# Schematic.net
KiCad netlist of a schematic drawn in Altium Designer
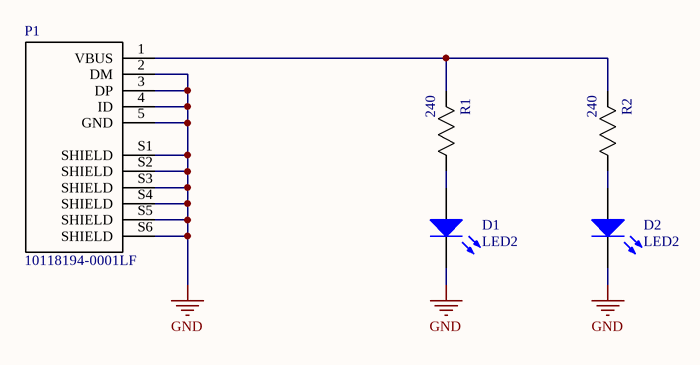
[diagram p0: Schematic.SchDoc]

(export (version "E")
  (design (tool "Eeschema 10.0.6"))
  (components
    (comp (ref "D1")
      (value "LED2")
      (footprint "3.2X1.6X1.1")
      (description "Typical RED, GREEN, YELLOW, AMBER GaAs LED")
      (libsource (lib "AltiumLibraries") (part "LED RED SMD"))
    )
    (comp (ref "D2")
      (value "LED2")
      (footprint "3.2X1.6X1.1")
      (description "Typical RED, GREEN, YELLOW, AMBER GaAs LED")
      (libsource (lib "AltiumLibraries") (part "LED RED SMD"))
    )
    (comp (ref "P1")
      (value "10118194-0001LF")
      (footprint "USB Micro B Receptacle")
      (description "USB - micro B USB 2.0 Receptacle Connector 5 Position Surface Mount, Right Angle; Through Hole")
      (fields (field (name "MF") "Amphenol ICC (FCI)"))
      (libsource (lib "AltiumLibraries") (part "USB Micro B Receptacle"))
    )
    (comp (ref "R1")
      (value "240")
      (footprint "0805")
      (description "RES SMD 240 OHM 5% 1/8W 0805")
      (fields (field (name "TOLERANCE") "5%"))
      (libsource (lib "AltiumLibraries") (part "RES 240.0 1/8W"))
    )
    (comp (ref "R2")
      (value "240")
      (footprint "0805")
      (description "RES SMD 240 OHM 5% 1/8W 0805")
      (fields (field (name "TOLERANCE") "5%"))
      (libsource (lib "AltiumLibraries") (part "RES 240.0 1/8W"))
    )
  )
  (nets
    (net (code "1") (name "GND") (class "Default")
      (node (ref "D1") (pin "2") (pinfunction "K_2") (pintype "passive"))
      (node (ref "D2") (pin "2") (pinfunction "K_2") (pintype "passive"))
      (node (ref "P1") (pin "2") (pinfunction "DM_2") (pintype "passive"))
      (node (ref "P1") (pin "3") (pinfunction "DP_3") (pintype "passive"))
      (node (ref "P1") (pin "4") (pinfunction "ID_4") (pintype "passive"))
      (node (ref "P1") (pin "5") (pinfunction "GND_5") (pintype "passive"))
      (node (ref "P1") (pin "S1") (pinfunction "SHIELD_S1") (pintype "passive"))
      (node (ref "P1") (pin "S2") (pinfunction "SHIELD_S2") (pintype "passive"))
      (node (ref "P1") (pin "S3") (pinfunction "SHIELD_S3") (pintype "passive"))
      (node (ref "P1") (pin "S4") (pinfunction "SHIELD_S4") (pintype "passive"))
      (node (ref "P1") (pin "S5") (pinfunction "SHIELD_S5") (pintype "passive"))
      (node (ref "P1") (pin "S6") (pinfunction "SHIELD_S6") (pintype "passive"))
    )
    (net (code "2") (name "Net-(D1-A)") (class "Default")
      (node (ref "D1") (pin "1") (pinfunction "A_1") (pintype "passive"))
      (node (ref "R1") (pin "1") (pinfunction "R1_1") (pintype "passive"))
    )
    (net (code "3") (name "Net-(D2-A)") (class "Default")
      (node (ref "D2") (pin "1") (pinfunction "A_1") (pintype "passive"))
      (node (ref "R2") (pin "1") (pinfunction "R1_1") (pintype "passive"))
    )
    (net (code "4") (name "Net-(P1-VBUS)") (class "Default")
      (node (ref "P1") (pin "1") (pinfunction "VBUS_1") (pintype "passive"))
      (node (ref "R1") (pin "2") (pinfunction "R2_2") (pintype "passive"))
      (node (ref "R2") (pin "2") (pinfunction "R2_2") (pintype "passive"))
    )
  )
)
